# GPIO_EXPANDER_B.net
KiCad netlist of a schematic drawn in Altium Designer
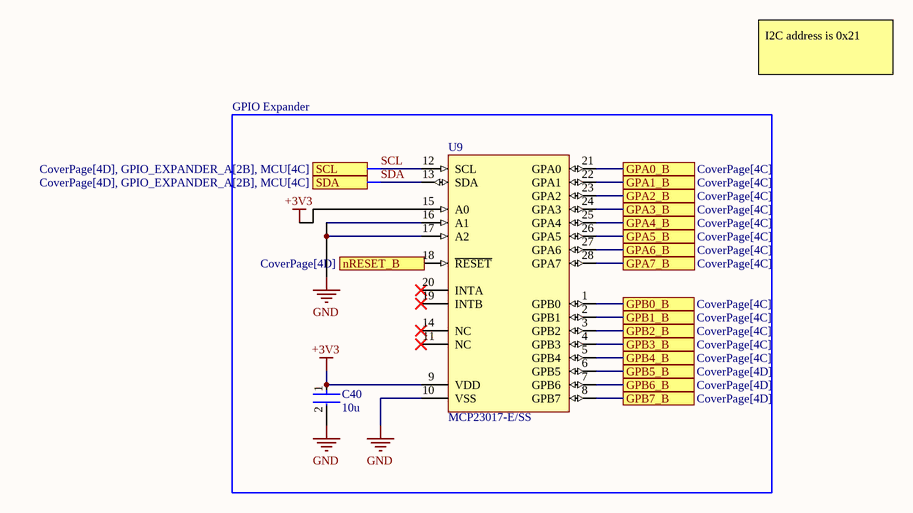
[diagram p0: GPIO_EXPANDER_B.SchDoc]

(export (version "E")
  (design (tool "Eeschema 10.0.6"))
  (components
    (comp (ref "C40")
      (value "10u")
      (footprint "FP-C0805C-DG-MFG")
      (description "CAP CER 10UF 10V X5R 0805")
      (fields (field (name "TOLERANCE") "10%") (field (name "MANUFACTURER PART NUMBER") "C0805C106K8PACTU"))
      (libsource (lib "Altium Content Vault") (part "11868f565c42a9108669ba33697ecf6"))
    )
    (comp (ref "U9")
      (value "MCP23017-E/SS")
      (footprint "SSOP-SS28_N")
      (description "16-Bit I/O Expander with Serial Interface, 28-Pin SSOP, Extended Temperature")
      (libsource (lib "Altium Content Vault") (part "PR-BUSIC-MCP23017-28"))
    )
  )
  (nets
    (net (code "1") (name "+3V3") (class "Default")
      (node (ref "C40") (pin "1") (pinfunction "1_1") (pintype "passive"))
      (node (ref "U9") (pin "15") (pinfunction "A0_15") (pintype "input"))
      (node (ref "U9") (pin "9") (pinfunction "VDD_9") (pintype "power_in"))
    )
    (net (code "2") (name "/GPA0_B") (class "Default")
      (node (ref "U9") (pin "21") (pinfunction "GPA0_21") (pintype "bidirectional"))
    )
    (net (code "3") (name "/GPA1_B") (class "Default")
      (node (ref "U9") (pin "22") (pinfunction "GPA1_22") (pintype "bidirectional"))
    )
    (net (code "4") (name "/GPA2_B") (class "Default")
      (node (ref "U9") (pin "23") (pinfunction "GPA2_23") (pintype "bidirectional"))
    )
    (net (code "5") (name "/GPA3_B") (class "Default")
      (node (ref "U9") (pin "24") (pinfunction "GPA3_24") (pintype "bidirectional"))
    )
    (net (code "6") (name "/GPA4_B") (class "Default")
      (node (ref "U9") (pin "25") (pinfunction "GPA4_25") (pintype "bidirectional"))
    )
    (net (code "7") (name "/GPA5_B") (class "Default")
      (node (ref "U9") (pin "26") (pinfunction "GPA5_26") (pintype "bidirectional"))
    )
    (net (code "8") (name "/GPA6_B") (class "Default")
      (node (ref "U9") (pin "27") (pinfunction "GPA6_27") (pintype "bidirectional"))
    )
    (net (code "9") (name "/GPA7_B") (class "Default")
      (node (ref "U9") (pin "28") (pinfunction "GPA7_28") (pintype "bidirectional"))
    )
    (net (code "10") (name "/GPB0_B") (class "Default")
      (node (ref "U9") (pin "1") (pinfunction "GPB0_1") (pintype "bidirectional"))
    )
    (net (code "11") (name "/GPB1_B") (class "Default")
      (node (ref "U9") (pin "2") (pinfunction "GPB1_2") (pintype "bidirectional"))
    )
    (net (code "12") (name "/GPB2_B") (class "Default")
      (node (ref "U9") (pin "3") (pinfunction "GPB2_3") (pintype "bidirectional"))
    )
    (net (code "13") (name "/GPB3_B") (class "Default")
      (node (ref "U9") (pin "4") (pinfunction "GPB3_4") (pintype "bidirectional"))
    )
    (net (code "14") (name "/GPB4_B") (class "Default")
      (node (ref "U9") (pin "5") (pinfunction "GPB4_5") (pintype "bidirectional"))
    )
    (net (code "15") (name "/GPB5_B") (class "Default")
      (node (ref "U9") (pin "6") (pinfunction "GPB5_6") (pintype "bidirectional"))
    )
    (net (code "16") (name "/GPB6_B") (class "Default")
      (node (ref "U9") (pin "7") (pinfunction "GPB6_7") (pintype "bidirectional"))
    )
    (net (code "17") (name "/GPB7_B") (class "Default")
      (node (ref "U9") (pin "8") (pinfunction "GPB7_8") (pintype "bidirectional"))
    )
    (net (code "18") (name "/SCL") (class "Default")
      (node (ref "U9") (pin "12") (pinfunction "SCL_12") (pintype "input"))
    )
    (net (code "19") (name "/SDA") (class "Default")
      (node (ref "U9") (pin "13") (pinfunction "SDA_13") (pintype "bidirectional"))
    )
    (net (code "21") (name "GND") (class "Default")
      (node (ref "C40") (pin "2") (pinfunction "2_2") (pintype "passive"))
      (node (ref "U9") (pin "10") (pinfunction "VSS_10") (pintype "power_in"))
      (node (ref "U9") (pin "16") (pinfunction "A1_16") (pintype "input"))
      (node (ref "U9") (pin "17") (pinfunction "A2_17") (pintype "input"))
    )
    (net (code "22") (name "unconnected-(U9-INTA-Pad20)") (class "Default")
      (node (ref "U9") (pin "20") (pinfunction "INTA_20") (pintype "open_collector+no_connect"))
    )
    (net (code "23") (name "unconnected-(U9-INTB-Pad19)") (class "Default")
      (node (ref "U9") (pin "19") (pinfunction "INTB_19") (pintype "open_collector+no_connect"))
    )
    (net (code "24") (name "unconnected-(U9-NC-Pad11)") (class "Default")
      (node (ref "U9") (pin "11") (pinfunction "NC_11") (pintype "passive+no_connect"))
    )
    (net (code "25") (name "unconnected-(U9-NC-Pad14)") (class "Default")
      (node (ref "U9") (pin "14") (pinfunction "NC_14") (pintype "passive+no_connect"))
    )
    (net (code "26") (name "unconnected-(U9-~{RESET}-Pad18)") (class "Default")
      (node (ref "U9") (pin "18") (pinfunction "~{RESET}_18") (pintype "input"))
    )
  )
)
